# Lights-ctrl_rev01.net
KiCad netlist of a schematic drawn in EAGLE
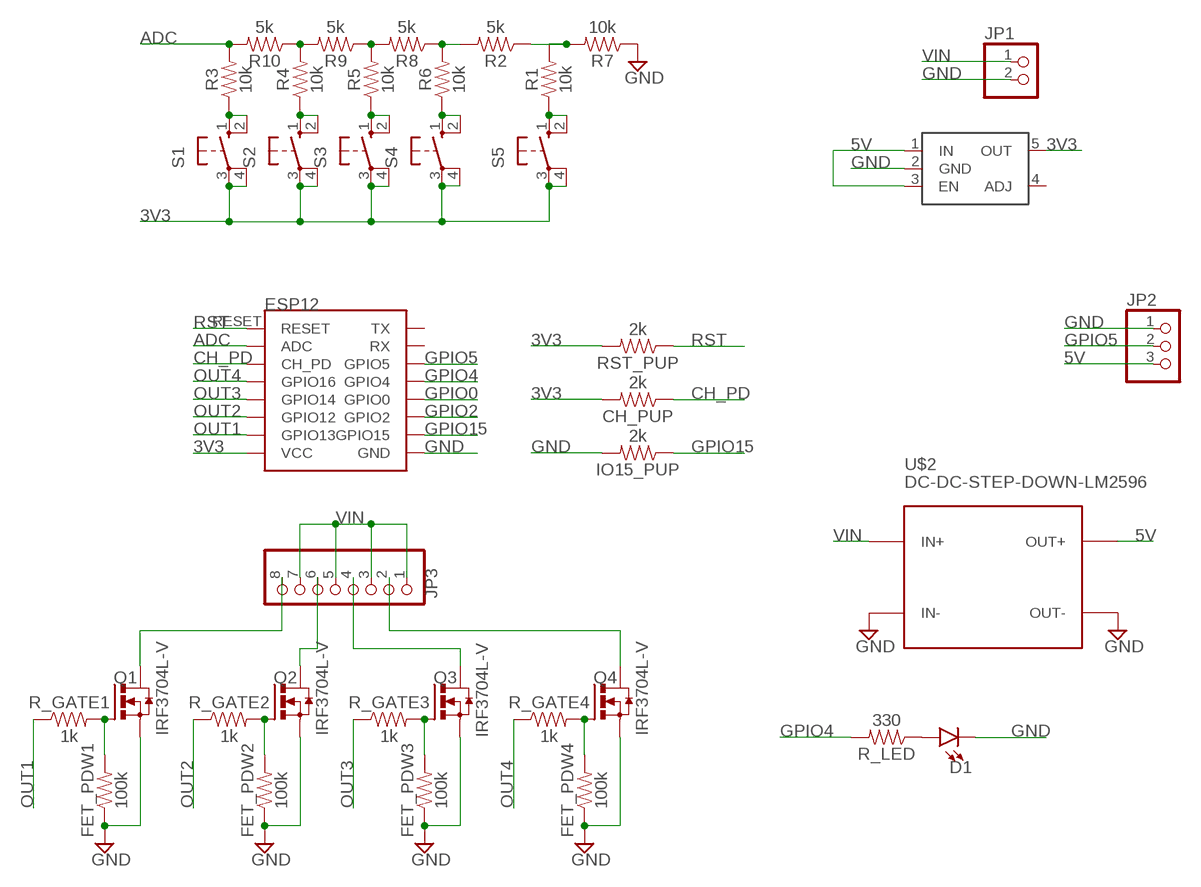
[diagram p0: schematic, sheet 1]

(export (version "E")
  (design (tool "Eeschema 10.0.6"))
  (components
    (comp (ref "CH_PUP")
      (value "2k")
      (footprint "eagle-import:0603")
      (libsource (lib "eagle-import") (part "200KOHM-0603-1/10W-1%"))
    )
    (comp (ref "D1")
      (value "LED5MM-KIT")
      (footprint "eagle-import:LED_5MM-KIT")
      (libsource (lib "eagle-import") (part "LED5MM-KIT"))
    )
    (comp (ref "FET_PDW1")
      (value "100k")
      (footprint "eagle-import:0603")
      (libsource (lib "eagle-import") (part "200KOHM-0603-1/10W-1%"))
    )
    (comp (ref "FET_PDW2")
      (value "100k")
      (footprint "eagle-import:0603")
      (libsource (lib "eagle-import") (part "200KOHM-0603-1/10W-1%"))
    )
    (comp (ref "FET_PDW3")
      (value "100k")
      (footprint "eagle-import:0603")
      (libsource (lib "eagle-import") (part "200KOHM-0603-1/10W-1%"))
    )
    (comp (ref "FET_PDW4")
      (value "100k")
      (footprint "eagle-import:0603")
      (libsource (lib "eagle-import") (part "200KOHM-0603-1/10W-1%"))
    )
    (comp (ref "IO15_PUP")
      (value "2k")
      (footprint "eagle-import:0603")
      (libsource (lib "eagle-import") (part "200KOHM-0603-1/10W-1%"))
    )
    (comp (ref "JP1")
      (value "PINHD-1X2")
      (footprint "eagle-import:1X02")
      (libsource (lib "eagle-import") (part "PINHD-1X2"))
    )
    (comp (ref "JP2")
      (value "PINHD-1X3")
      (footprint "eagle-import:1X03")
      (libsource (lib "eagle-import") (part "PINHD-1X3"))
    )
    (comp (ref "JP3")
      (value "PINHD-1X8/90")
      (footprint "eagle-import:1X08_90")
      (libsource (lib "eagle-import") (part "PINHD-1X8/90"))
    )
    (comp (ref "Q1")
      (value "IRF3704L-V")
      (footprint "eagle-import:TO262-V")
      (libsource (lib "eagle-import") (part "IRF3704L-V"))
    )
    (comp (ref "Q2")
      (value "IRF3704L-V")
      (footprint "eagle-import:TO262-V")
      (libsource (lib "eagle-import") (part "IRF3704L-V"))
    )
    (comp (ref "Q3")
      (value "IRF3704L-V")
      (footprint "eagle-import:TO262-V")
      (libsource (lib "eagle-import") (part "IRF3704L-V"))
    )
    (comp (ref "Q4")
      (value "IRF3704L-V")
      (footprint "eagle-import:TO262-V")
      (libsource (lib "eagle-import") (part "IRF3704L-V"))
    )
    (comp (ref "R1")
      (value "10k")
      (footprint "eagle-import:0603")
      (libsource (lib "eagle-import") (part "200KOHM-0603-1/10W-1%"))
    )
    (comp (ref "R2")
      (value "5k")
      (footprint "eagle-import:0603")
      (libsource (lib "eagle-import") (part "200KOHM-0603-1/10W-1%"))
    )
    (comp (ref "R3")
      (value "10k")
      (footprint "eagle-import:0603")
      (libsource (lib "eagle-import") (part "200KOHM-0603-1/10W-1%"))
    )
    (comp (ref "R4")
      (value "10k")
      (footprint "eagle-import:0603")
      (libsource (lib "eagle-import") (part "200KOHM-0603-1/10W-1%"))
    )
    (comp (ref "R5")
      (value "10k")
      (footprint "eagle-import:0603")
      (libsource (lib "eagle-import") (part "200KOHM-0603-1/10W-1%"))
    )
    (comp (ref "R6")
      (value "10k")
      (footprint "eagle-import:0603")
      (libsource (lib "eagle-import") (part "200KOHM-0603-1/10W-1%"))
    )
    (comp (ref "R7")
      (value "10k")
      (footprint "eagle-import:0603")
      (libsource (lib "eagle-import") (part "200KOHM-0603-1/10W-1%"))
    )
    (comp (ref "R8")
      (value "5k")
      (footprint "eagle-import:0603")
      (libsource (lib "eagle-import") (part "200KOHM-0603-1/10W-1%"))
    )
    (comp (ref "R9")
      (value "5k")
      (footprint "eagle-import:0603")
      (libsource (lib "eagle-import") (part "200KOHM-0603-1/10W-1%"))
    )
    (comp (ref "R10")
      (value "5k")
      (footprint "eagle-import:0603")
      (libsource (lib "eagle-import") (part "200KOHM-0603-1/10W-1%"))
    )
    (comp (ref "RST_PUP")
      (value "2k")
      (footprint "eagle-import:0603")
      (libsource (lib "eagle-import") (part "200KOHM-0603-1/10W-1%"))
    )
    (comp (ref "R_GATE1")
      (value "1k")
      (footprint "eagle-import:0603")
      (libsource (lib "eagle-import") (part "200KOHM-0603-1/10W-1%"))
    )
    (comp (ref "R_GATE2")
      (value "1k")
      (footprint "eagle-import:0603")
      (libsource (lib "eagle-import") (part "200KOHM-0603-1/10W-1%"))
    )
    (comp (ref "R_GATE3")
      (value "1k")
      (footprint "eagle-import:0603")
      (libsource (lib "eagle-import") (part "200KOHM-0603-1/10W-1%"))
    )
    (comp (ref "R_GATE4")
      (value "1k")
      (footprint "eagle-import:0603")
      (libsource (lib "eagle-import") (part "200KOHM-0603-1/10W-1%"))
    )
    (comp (ref "R_LED")
      (value "330")
      (footprint "eagle-import:0603")
      (libsource (lib "eagle-import") (part "200KOHM-0603-1/10W-1%"))
    )
    (comp (ref "S1")
      (value "10-XX")
      (footprint "eagle-import:B3F-10XX")
      (fields (field (name "MPN") "B3F-1000"))
      (libsource (lib "eagle-import") (part "10-XX"))
    )
    (comp (ref "S2")
      (value "10-XX")
      (footprint "eagle-import:B3F-10XX")
      (fields (field (name "MPN") "B3F-1000"))
      (libsource (lib "eagle-import") (part "10-XX"))
    )
    (comp (ref "S3")
      (value "10-XX")
      (footprint "eagle-import:B3F-10XX")
      (fields (field (name "MPN") "B3F-1000"))
      (libsource (lib "eagle-import") (part "10-XX"))
    )
    (comp (ref "S4")
      (value "10-XX")
      (footprint "eagle-import:B3F-10XX")
      (fields (field (name "MPN") "B3F-1000"))
      (libsource (lib "eagle-import") (part "10-XX"))
    )
    (comp (ref "S5")
      (value "10-XX")
      (footprint "eagle-import:B3F-10XX")
      (fields (field (name "MPN") "B3F-1000"))
      (libsource (lib "eagle-import") (part "10-XX"))
    )
    (comp (ref "U$1")
      (value "ESP12E-CASTELLATED")
      (footprint "eagle-import:ESP12E-CASTELLATED")
      (libsource (lib "eagle-import") (part "ESP12E-CASTELLATED"))
    )
    (comp (ref "U$2")
      (value "DC-DC-STEP-DOWN-LM2596")
      (footprint "eagle-import:DC-DC-STEP-DOWN-LM2596")
      (libsource (lib "eagle-import") (part "DC-DC-STEP-DOWN-LM2596"))
    )
    (comp (ref "U$3")
      (value "MIC5219-BM5")
      (footprint "eagle-import:SOT-23-5")
      (libsource (lib "eagle-import") (part "MIC5219-BM5"))
    )
  )
  (nets
    (net (code "1") (name "/3V3") (class "Default")
      (node (ref "CH_PUP") (pin "2") (pinfunction "2_2") (pintype "passive"))
      (node (ref "RST_PUP") (pin "2") (pinfunction "2_2") (pintype "passive"))
      (node (ref "S1") (pin "3") (pinfunction "P_3") (pintype "passive"))
      (node (ref "S1") (pin "4") (pinfunction "P1_4") (pintype "passive"))
      (node (ref "S2") (pin "3") (pinfunction "P_3") (pintype "passive"))
      (node (ref "S2") (pin "4") (pinfunction "P1_4") (pintype "passive"))
      (node (ref "S3") (pin "3") (pinfunction "P_3") (pintype "passive"))
      (node (ref "S3") (pin "4") (pinfunction "P1_4") (pintype "passive"))
      (node (ref "S4") (pin "3") (pinfunction "P_3") (pintype "passive"))
      (node (ref "S4") (pin "4") (pinfunction "P1_4") (pintype "passive"))
      (node (ref "S5") (pin "3") (pinfunction "P_3") (pintype "passive"))
      (node (ref "S5") (pin "4") (pinfunction "P1_4") (pintype "passive"))
      (node (ref "U$1") (pin "VCC") (pinfunction "VCC_VCC") (pintype "bidirectional"))
      (node (ref "U$3") (pin "5") (pinfunction "OUT_5") (pintype "bidirectional"))
    )
    (net (code "2") (name "/5V") (class "Default")
      (node (ref "JP2") (pin "3") (pinfunction "3_3") (pintype "passive"))
      (node (ref "U$2") (pin "OUT+") (pinfunction "OUT+_OUT+") (pintype "bidirectional"))
      (node (ref "U$3") (pin "1") (pinfunction "IN_1") (pintype "bidirectional"))
      (node (ref "U$3") (pin "3") (pinfunction "EN_3") (pintype "bidirectional"))
    )
    (net (code "3") (name "/ADC") (class "Default")
      (node (ref "R10") (pin "2") (pinfunction "2_2") (pintype "passive"))
      (node (ref "R3") (pin "2") (pinfunction "2_2") (pintype "passive"))
      (node (ref "U$1") (pin "ADC") (pinfunction "ADC_ADC") (pintype "bidirectional"))
    )
    (net (code "4") (name "/CH_PD") (class "Default")
      (node (ref "CH_PUP") (pin "1") (pinfunction "1_1") (pintype "passive"))
      (node (ref "U$1") (pin "CH_PD") (pinfunction "CH_PD_CH_PD") (pintype "bidirectional"))
    )
    (net (code "5") (name "/GPIO0") (class "Default")
      (node (ref "U$1") (pin "GPIO0") (pinfunction "GPIO0_GPIO0") (pintype "bidirectional"))
    )
    (net (code "6") (name "/GPIO2") (class "Default")
      (node (ref "U$1") (pin "GPIO2") (pinfunction "GPIO2_GPIO2") (pintype "bidirectional"))
    )
    (net (code "7") (name "/GPIO4") (class "Default")
      (node (ref "R_LED") (pin "2") (pinfunction "2_2") (pintype "passive"))
      (node (ref "U$1") (pin "GPIO4") (pinfunction "GPIO4_GPIO4") (pintype "bidirectional"))
    )
    (net (code "8") (name "/GPIO5") (class "Default")
      (node (ref "JP2") (pin "2") (pinfunction "2_2") (pintype "passive"))
      (node (ref "U$1") (pin "GPIO5") (pinfunction "GPIO5_GPIO5") (pintype "bidirectional"))
    )
    (net (code "9") (name "/GPIO15") (class "Default")
      (node (ref "IO15_PUP") (pin "1") (pinfunction "1_1") (pintype "passive"))
      (node (ref "U$1") (pin "GPIO15") (pinfunction "GPIO15_GPIO15") (pintype "bidirectional"))
    )
    (net (code "10") (name "/OUT1") (class "Default")
      (node (ref "R_GATE1") (pin "1") (pinfunction "1_1") (pintype "passive"))
      (node (ref "U$1") (pin "GPIO13") (pinfunction "GPIO13_GPIO13") (pintype "bidirectional"))
    )
    (net (code "11") (name "/OUT2") (class "Default")
      (node (ref "R_GATE2") (pin "1") (pinfunction "1_1") (pintype "passive"))
      (node (ref "U$1") (pin "GPIO12") (pinfunction "GPIO12_GPIO12") (pintype "bidirectional"))
    )
    (net (code "12") (name "/OUT3") (class "Default")
      (node (ref "R_GATE3") (pin "1") (pinfunction "1_1") (pintype "passive"))
      (node (ref "U$1") (pin "GPIO14") (pinfunction "GPIO14_GPIO14") (pintype "bidirectional"))
    )
    (net (code "13") (name "/OUT4") (class "Default")
      (node (ref "R_GATE4") (pin "1") (pinfunction "1_1") (pintype "passive"))
      (node (ref "U$1") (pin "GPIO16") (pinfunction "GPIO16_GPIO16") (pintype "bidirectional"))
    )
    (net (code "14") (name "/RST") (class "Default")
      (node (ref "RST_PUP") (pin "1") (pinfunction "1_1") (pintype "passive"))
      (node (ref "U$1") (pin "RESET") (pinfunction "RESET_RESET") (pintype "bidirectional"))
    )
    (net (code "15") (name "/VIN") (class "Default")
      (node (ref "JP1") (pin "1") (pinfunction "1_1") (pintype "passive"))
      (node (ref "JP3") (pin "1") (pinfunction "1_1") (pintype "passive"))
      (node (ref "JP3") (pin "3") (pinfunction "3_3") (pintype "passive"))
      (node (ref "JP3") (pin "5") (pinfunction "5_5") (pintype "passive"))
      (node (ref "JP3") (pin "7") (pinfunction "7_7") (pintype "passive"))
      (node (ref "U$2") (pin "IN+") (pinfunction "IN+_IN+") (pintype "bidirectional"))
    )
    (net (code "16") (name "GND") (class "Default")
      (node (ref "D1") (pin "K") (pinfunction "C_K") (pintype "passive"))
      (node (ref "FET_PDW1") (pin "1") (pinfunction "1_1") (pintype "passive"))
      (node (ref "FET_PDW2") (pin "1") (pinfunction "1_1") (pintype "passive"))
      (node (ref "FET_PDW3") (pin "1") (pinfunction "1_1") (pintype "passive"))
      (node (ref "FET_PDW4") (pin "1") (pinfunction "1_1") (pintype "passive"))
      (node (ref "IO15_PUP") (pin "2") (pinfunction "2_2") (pintype "passive"))
      (node (ref "JP1") (pin "2") (pinfunction "2_2") (pintype "passive"))
      (node (ref "JP2") (pin "1") (pinfunction "1_1") (pintype "passive"))
      (node (ref "Q1") (pin "3") (pinfunction "S_3") (pintype "passive"))
      (node (ref "Q2") (pin "3") (pinfunction "S_3") (pintype "passive"))
      (node (ref "Q3") (pin "3") (pinfunction "S_3") (pintype "passive"))
      (node (ref "Q4") (pin "3") (pinfunction "S_3") (pintype "passive"))
      (node (ref "R7") (pin "1") (pinfunction "1_1") (pintype "passive"))
      (node (ref "U$1") (pin "GND") (pinfunction "GND_GND") (pintype "bidirectional"))
      (node (ref "U$2") (pin "IN-") (pinfunction "IN-_IN-") (pintype "bidirectional"))
      (node (ref "U$2") (pin "OUT-") (pinfunction "OUT-_OUT-") (pintype "bidirectional"))
      (node (ref "U$3") (pin "2") (pinfunction "GND_2") (pintype "bidirectional"))
    )
    (net (code "17") (name "Net-(D1-PadA)") (class "Default")
      (node (ref "D1") (pin "A") (pinfunction "A_A") (pintype "passive"))
      (node (ref "R_LED") (pin "1") (pinfunction "1_1") (pintype "passive"))
    )
    (net (code "18") (name "Net-(Q1-D)") (class "Default")
      (node (ref "JP3") (pin "8") (pinfunction "8_8") (pintype "passive"))
      (node (ref "Q1") (pin "2") (pinfunction "D_2") (pintype "passive"))
    )
    (net (code "19") (name "Net-(Q1-G)") (class "Default")
      (node (ref "FET_PDW1") (pin "2") (pinfunction "2_2") (pintype "passive"))
      (node (ref "Q1") (pin "1") (pinfunction "G_1") (pintype "passive"))
      (node (ref "R_GATE1") (pin "2") (pinfunction "2_2") (pintype "passive"))
    )
    (net (code "20") (name "Net-(Q2-D)") (class "Default")
      (node (ref "JP3") (pin "6") (pinfunction "6_6") (pintype "passive"))
      (node (ref "Q2") (pin "2") (pinfunction "D_2") (pintype "passive"))
    )
    (net (code "21") (name "Net-(Q2-G)") (class "Default")
      (node (ref "FET_PDW2") (pin "2") (pinfunction "2_2") (pintype "passive"))
      (node (ref "Q2") (pin "1") (pinfunction "G_1") (pintype "passive"))
      (node (ref "R_GATE2") (pin "2") (pinfunction "2_2") (pintype "passive"))
    )
    (net (code "22") (name "Net-(Q3-D)") (class "Default")
      (node (ref "JP3") (pin "4") (pinfunction "4_4") (pintype "passive"))
      (node (ref "Q3") (pin "2") (pinfunction "D_2") (pintype "passive"))
    )
    (net (code "23") (name "Net-(Q3-G)") (class "Default")
      (node (ref "FET_PDW3") (pin "2") (pinfunction "2_2") (pintype "passive"))
      (node (ref "Q3") (pin "1") (pinfunction "G_1") (pintype "passive"))
      (node (ref "R_GATE3") (pin "2") (pinfunction "2_2") (pintype "passive"))
    )
    (net (code "24") (name "Net-(Q4-D)") (class "Default")
      (node (ref "JP3") (pin "2") (pinfunction "2_2") (pintype "passive"))
      (node (ref "Q4") (pin "2") (pinfunction "D_2") (pintype "passive"))
    )
    (net (code "25") (name "Net-(Q4-G)") (class "Default")
      (node (ref "FET_PDW4") (pin "2") (pinfunction "2_2") (pintype "passive"))
      (node (ref "Q4") (pin "1") (pinfunction "G_1") (pintype "passive"))
      (node (ref "R_GATE4") (pin "2") (pinfunction "2_2") (pintype "passive"))
    )
    (net (code "26") (name "Net-(R1-Pad2)") (class "Default")
      (node (ref "R1") (pin "2") (pinfunction "2_2") (pintype "passive"))
      (node (ref "R2") (pin "1") (pinfunction "1_1") (pintype "passive"))
      (node (ref "R7") (pin "2") (pinfunction "2_2") (pintype "passive"))
    )
    (net (code "27") (name "Net-(R2-Pad2)") (class "Default")
      (node (ref "R2") (pin "2") (pinfunction "2_2") (pintype "passive"))
      (node (ref "R6") (pin "2") (pinfunction "2_2") (pintype "passive"))
      (node (ref "R8") (pin "1") (pinfunction "1_1") (pintype "passive"))
    )
    (net (code "28") (name "Net-(R5-Pad2)") (class "Default")
      (node (ref "R5") (pin "2") (pinfunction "2_2") (pintype "passive"))
      (node (ref "R8") (pin "2") (pinfunction "2_2") (pintype "passive"))
      (node (ref "R9") (pin "1") (pinfunction "1_1") (pintype "passive"))
    )
    (net (code "29") (name "Net-(R10-Pad1)") (class "Default")
      (node (ref "R10") (pin "1") (pinfunction "1_1") (pintype "passive"))
      (node (ref "R4") (pin "2") (pinfunction "2_2") (pintype "passive"))
      (node (ref "R9") (pin "2") (pinfunction "2_2") (pintype "passive"))
    )
    (net (code "30") (name "Net-(S1-S)") (class "Default")
      (node (ref "R3") (pin "1") (pinfunction "1_1") (pintype "passive"))
      (node (ref "S1") (pin "1") (pinfunction "S_1") (pintype "passive"))
      (node (ref "S1") (pin "2") (pinfunction "S1_2") (pintype "passive"))
    )
    (net (code "31") (name "Net-(S2-S)") (class "Default")
      (node (ref "R4") (pin "1") (pinfunction "1_1") (pintype "passive"))
      (node (ref "S2") (pin "1") (pinfunction "S_1") (pintype "passive"))
      (node (ref "S2") (pin "2") (pinfunction "S1_2") (pintype "passive"))
    )
    (net (code "32") (name "Net-(S3-S)") (class "Default")
      (node (ref "R5") (pin "1") (pinfunction "1_1") (pintype "passive"))
      (node (ref "S3") (pin "1") (pinfunction "S_1") (pintype "passive"))
      (node (ref "S3") (pin "2") (pinfunction "S1_2") (pintype "passive"))
    )
    (net (code "33") (name "Net-(S4-S)") (class "Default")
      (node (ref "R6") (pin "1") (pinfunction "1_1") (pintype "passive"))
      (node (ref "S4") (pin "1") (pinfunction "S_1") (pintype "passive"))
      (node (ref "S4") (pin "2") (pinfunction "S1_2") (pintype "passive"))
    )
    (net (code "34") (name "Net-(S5-S)") (class "Default")
      (node (ref "R1") (pin "1") (pinfunction "1_1") (pintype "passive"))
      (node (ref "S5") (pin "1") (pinfunction "S_1") (pintype "passive"))
      (node (ref "S5") (pin "2") (pinfunction "S1_2") (pintype "passive"))
    )
    (net (code "35") (name "unconnected-(U$1-PadRX)") (class "Default")
      (node (ref "U$1") (pin "RX") (pinfunction "RX_RX") (pintype "bidirectional"))
    )
    (net (code "36") (name "unconnected-(U$1-PadTX)") (class "Default")
      (node (ref "U$1") (pin "TX") (pinfunction "TX_TX") (pintype "bidirectional"))
    )
    (net (code "37") (name "unconnected-(U$3-ADJ-Pad4)") (class "Default")
      (node (ref "U$3") (pin "4") (pinfunction "ADJ_4") (pintype "bidirectional"))
    )
  )
)
